# Esquema_01_guilherme.net
KiCad netlist of a schematic drawn in EAGLE
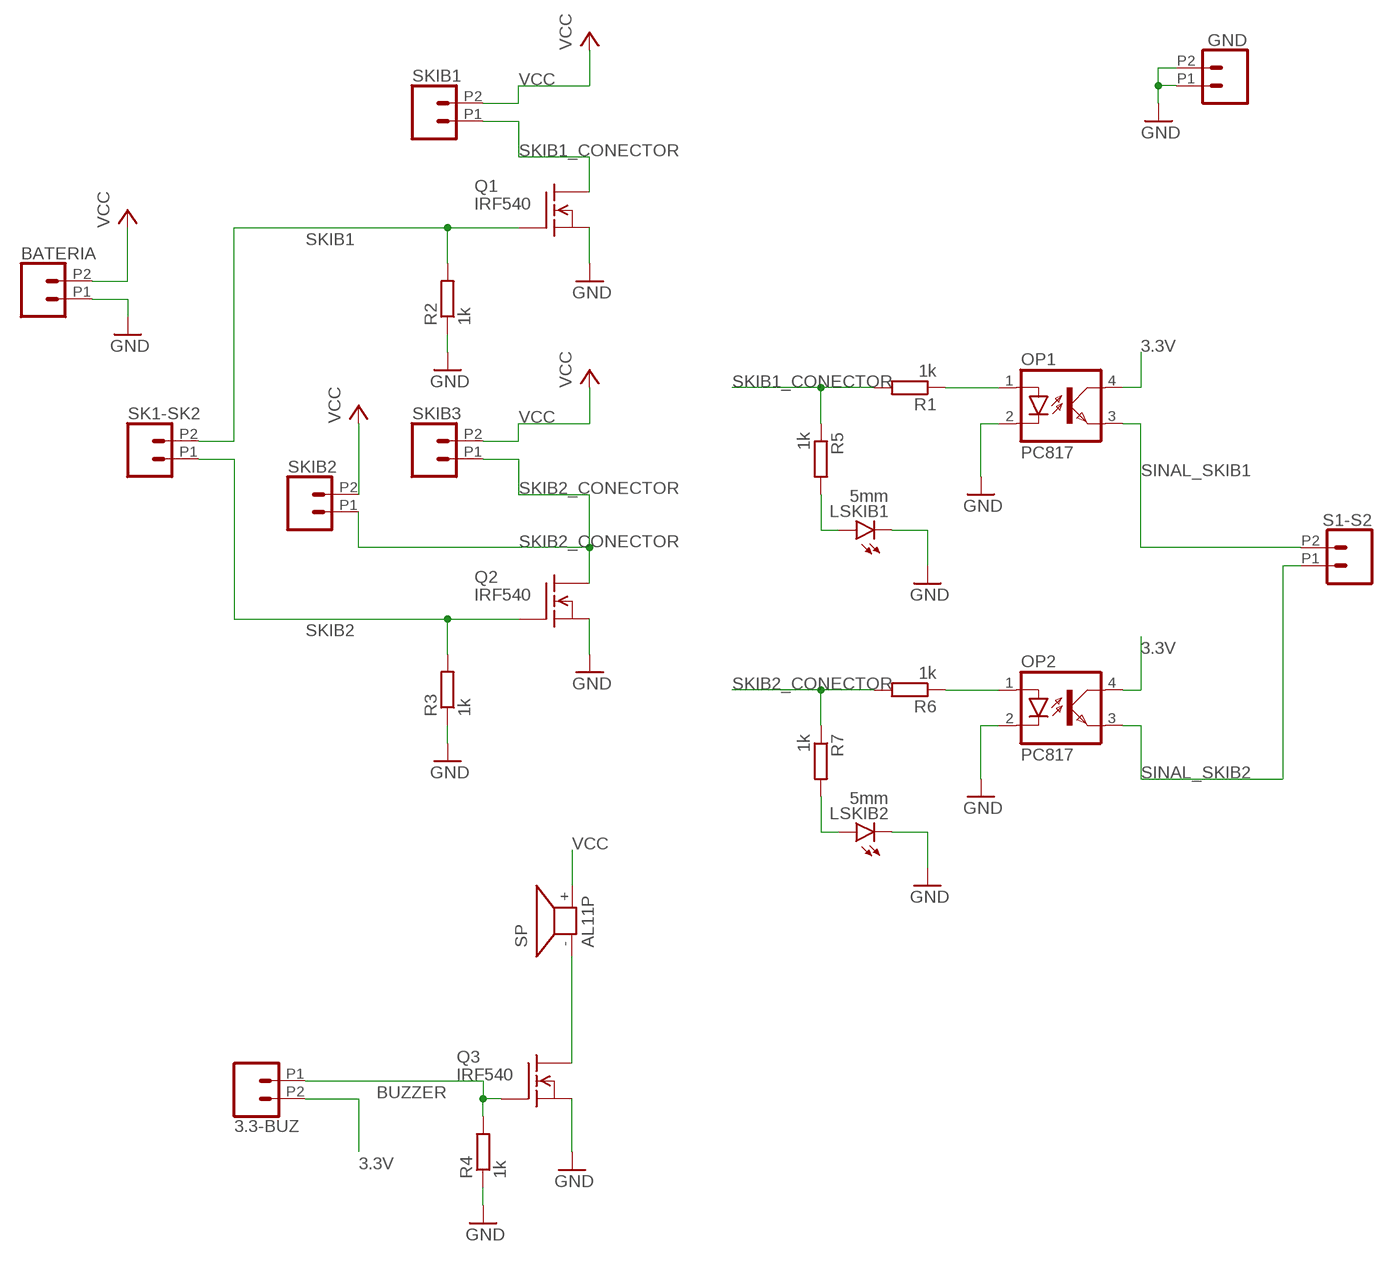
[diagram p0: schematic, sheet 1]

(export (version "E")
  (design (tool "Eeschema 10.0.6"))
  (components
    (comp (ref "3.3-BUZ")
      (value "CONN_022.54MM_SCREWTERM")
      (footprint "eagle-import:1X02_2.54_SCREWTERM")
      (libsource (lib "eagle-import") (part "CONN_022.54MM_SCREWTERM"))
    )
    (comp (ref "BATERIA")
      (value "CONN_022.54MM_SCREWTERM")
      (footprint "eagle-import:1X02_2.54_SCREWTERM")
      (libsource (lib "eagle-import") (part "CONN_022.54MM_SCREWTERM"))
    )
    (comp (ref "GND")
      (value "CONN_022.54MM_SCREWTERM")
      (footprint "eagle-import:1X02_2.54_SCREWTERM")
      (libsource (lib "eagle-import") (part "CONN_022.54MM_SCREWTERM"))
    )
    (comp (ref "LSKIB1")
      (value "5mm")
      (footprint "eagle-import:LED5MM")
      (libsource (lib "eagle-import") (part "LED5MM"))
    )
    (comp (ref "LSKIB2")
      (value "5mm")
      (footprint "eagle-import:LED5MM")
      (libsource (lib "eagle-import") (part "LED5MM"))
    )
    (comp (ref "OP1")
      (value "PC817")
      (footprint "eagle-import:DIL04")
      (fields (field (name "MPN") "PC817X4J000F"))
      (libsource (lib "eagle-import") (part "PC817"))
    )
    (comp (ref "OP2")
      (value "PC817")
      (footprint "eagle-import:DIL04")
      (fields (field (name "MPN") "PC817X4J000F"))
      (libsource (lib "eagle-import") (part "PC817"))
    )
    (comp (ref "Q1")
      (value "IRF540")
      (footprint "eagle-import:TO220")
      (libsource (lib "eagle-import") (part "IRF540"))
    )
    (comp (ref "Q2")
      (value "IRF540")
      (footprint "eagle-import:TO220")
      (libsource (lib "eagle-import") (part "IRF540"))
    )
    (comp (ref "Q3")
      (value "IRF540")
      (footprint "eagle-import:TO220")
      (libsource (lib "eagle-import") (part "IRF540"))
    )
    (comp (ref "R1")
      (value "1k")
      (footprint "eagle-import:0207_10")
      (libsource (lib "eagle-import") (part "R-EU_0207/10"))
    )
    (comp (ref "R2")
      (value "1k")
      (footprint "eagle-import:0207_10")
      (libsource (lib "eagle-import") (part "R-EU_0207/10"))
    )
    (comp (ref "R3")
      (value "1k")
      (footprint "eagle-import:0207_10")
      (libsource (lib "eagle-import") (part "R-EU_0207/10"))
    )
    (comp (ref "R4")
      (value "1k")
      (footprint "eagle-import:0207_10")
      (libsource (lib "eagle-import") (part "R-EU_0207/10"))
    )
    (comp (ref "R5")
      (value "1k")
      (footprint "eagle-import:0207_10")
      (libsource (lib "eagle-import") (part "R-EU_0207/10"))
    )
    (comp (ref "R6")
      (value "1k")
      (footprint "eagle-import:0207_10")
      (libsource (lib "eagle-import") (part "R-EU_0207/10"))
    )
    (comp (ref "R7")
      (value "1k")
      (footprint "eagle-import:0207_10")
      (libsource (lib "eagle-import") (part "R-EU_0207/10"))
    )
    (comp (ref "S1-S2")
      (value "CONN_022.54MM_SCREWTERM")
      (footprint "eagle-import:1X02_2.54_SCREWTERM")
      (libsource (lib "eagle-import") (part "CONN_022.54MM_SCREWTERM"))
    )
    (comp (ref "SK1-SK2")
      (value "CONN_022.54MM_SCREWTERM")
      (footprint "eagle-import:1X02_2.54_SCREWTERM")
      (libsource (lib "eagle-import") (part "CONN_022.54MM_SCREWTERM"))
    )
    (comp (ref "SKIB1")
      (value "CONN_022.54MM_SCREWTERM")
      (footprint "eagle-import:1X02_2.54_SCREWTERM")
      (libsource (lib "eagle-import") (part "CONN_022.54MM_SCREWTERM"))
    )
    (comp (ref "SKIB2")
      (value "CONN_022.54MM_SCREWTERM")
      (footprint "eagle-import:1X02_2.54_SCREWTERM")
      (libsource (lib "eagle-import") (part "CONN_022.54MM_SCREWTERM"))
    )
    (comp (ref "SKIB3")
      (value "CONN_022.54MM_SCREWTERM")
      (footprint "eagle-import:1X02_2.54_SCREWTERM")
      (libsource (lib "eagle-import") (part "CONN_022.54MM_SCREWTERM"))
    )
    (comp (ref "SP")
      (value "AL11P")
      (footprint "eagle-import:AL11P")
      (libsource (lib "eagle-import") (part "AL11P"))
    )
  )
  (nets
    (net (code "1") (name "/3.3V") (class "Default")
      (node (ref "3.3-BUZ") (pin "P2") (pinfunction "2_P2") (pintype "passive"))
      (node (ref "OP1") (pin "4") (pinfunction "COL_4") (pintype "passive"))
      (node (ref "OP2") (pin "4") (pinfunction "COL_4") (pintype "passive"))
    )
    (net (code "2") (name "/BUZZER") (class "Default")
      (node (ref "3.3-BUZ") (pin "P1") (pinfunction "1_P1") (pintype "passive"))
      (node (ref "Q3") (pin "1") (pinfunction "G_1") (pintype "passive"))
      (node (ref "R4") (pin "2") (pinfunction "2_2") (pintype "passive"))
    )
    (net (code "3") (name "/SINAL_SKIB1") (class "Default")
      (node (ref "OP1") (pin "3") (pinfunction "EMIT_3") (pintype "passive"))
      (node (ref "S1-S2") (pin "P2") (pinfunction "2_P2") (pintype "passive"))
    )
    (net (code "4") (name "/SINAL_SKIB2") (class "Default")
      (node (ref "OP2") (pin "3") (pinfunction "EMIT_3") (pintype "passive"))
      (node (ref "S1-S2") (pin "P1") (pinfunction "1_P1") (pintype "passive"))
    )
    (net (code "5") (name "/SKIB1") (class "Default")
      (node (ref "Q1") (pin "1") (pinfunction "G_1") (pintype "passive"))
      (node (ref "R2") (pin "2") (pinfunction "2_2") (pintype "passive"))
      (node (ref "SK1-SK2") (pin "P2") (pinfunction "2_P2") (pintype "passive"))
    )
    (net (code "6") (name "/SKIB1_CONECTOR") (class "Default")
      (node (ref "Q1") (pin "2") (pinfunction "D_2") (pintype "passive"))
      (node (ref "R1") (pin "2") (pinfunction "2_2") (pintype "passive"))
      (node (ref "R5") (pin "1") (pinfunction "1_1") (pintype "passive"))
      (node (ref "SKIB1") (pin "P1") (pinfunction "1_P1") (pintype "passive"))
    )
    (net (code "7") (name "/SKIB2") (class "Default")
      (node (ref "Q2") (pin "1") (pinfunction "G_1") (pintype "passive"))
      (node (ref "R3") (pin "2") (pinfunction "2_2") (pintype "passive"))
      (node (ref "SK1-SK2") (pin "P1") (pinfunction "1_P1") (pintype "passive"))
    )
    (net (code "8") (name "/SKIB2_CONECTOR") (class "Default")
      (node (ref "Q2") (pin "2") (pinfunction "D_2") (pintype "passive"))
      (node (ref "R6") (pin "2") (pinfunction "2_2") (pintype "passive"))
      (node (ref "R7") (pin "1") (pinfunction "1_1") (pintype "passive"))
      (node (ref "SKIB2") (pin "P1") (pinfunction "1_P1") (pintype "passive"))
      (node (ref "SKIB3") (pin "P1") (pinfunction "1_P1") (pintype "passive"))
    )
    (net (code "9") (name "GND") (class "Default")
      (node (ref "BATERIA") (pin "P1") (pinfunction "1_P1") (pintype "passive"))
      (node (ref "GND") (pin "P1") (pinfunction "1_P1") (pintype "passive"))
      (node (ref "GND") (pin "P2") (pinfunction "2_P2") (pintype "passive"))
      (node (ref "LSKIB1") (pin "K") (pinfunction "C_K") (pintype "passive"))
      (node (ref "LSKIB2") (pin "K") (pinfunction "C_K") (pintype "passive"))
      (node (ref "OP1") (pin "2") (pinfunction "C_2") (pintype "passive"))
      (node (ref "OP2") (pin "2") (pinfunction "C_2") (pintype "passive"))
      (node (ref "Q1") (pin "3") (pinfunction "S_3") (pintype "passive"))
      (node (ref "Q2") (pin "3") (pinfunction "S_3") (pintype "passive"))
      (node (ref "Q3") (pin "3") (pinfunction "S_3") (pintype "passive"))
      (node (ref "R2") (pin "1") (pinfunction "1_1") (pintype "passive"))
      (node (ref "R3") (pin "1") (pinfunction "1_1") (pintype "passive"))
      (node (ref "R4") (pin "1") (pinfunction "1_1") (pintype "passive"))
    )
    (net (code "10") (name "Net-(LSKIB1-PadA)") (class "Default")
      (node (ref "LSKIB1") (pin "A") (pinfunction "A_A") (pintype "passive"))
      (node (ref "R5") (pin "2") (pinfunction "2_2") (pintype "passive"))
    )
    (net (code "11") (name "Net-(LSKIB2-PadA)") (class "Default")
      (node (ref "LSKIB2") (pin "A") (pinfunction "A_A") (pintype "passive"))
      (node (ref "R7") (pin "2") (pinfunction "2_2") (pintype "passive"))
    )
    (net (code "12") (name "Net-(OP1-A)") (class "Default")
      (node (ref "OP1") (pin "1") (pinfunction "A_1") (pintype "passive"))
      (node (ref "R1") (pin "1") (pinfunction "1_1") (pintype "passive"))
    )
    (net (code "13") (name "Net-(OP2-A)") (class "Default")
      (node (ref "OP2") (pin "1") (pinfunction "A_1") (pintype "passive"))
      (node (ref "R6") (pin "1") (pinfunction "1_1") (pintype "passive"))
    )
    (net (code "14") (name "Net-(Q3-D)") (class "Default")
      (node (ref "Q3") (pin "2") (pinfunction "D_2") (pintype "passive"))
      (node (ref "SP") (pin "-") (pinfunction "1_-") (pintype "passive"))
    )
    (net (code "15") (name "VCC") (class "Default")
      (node (ref "BATERIA") (pin "P2") (pinfunction "2_P2") (pintype "passive"))
      (node (ref "SKIB1") (pin "P2") (pinfunction "2_P2") (pintype "passive"))
      (node (ref "SKIB2") (pin "P2") (pinfunction "2_P2") (pintype "passive"))
      (node (ref "SKIB3") (pin "P2") (pinfunction "2_P2") (pintype "passive"))
      (node (ref "SP") (pin "+") (pinfunction "2_+") (pintype "passive"))
    )
  )
)
